# pi-crust.net
KiCad netlist of a schematic drawn in EAGLE
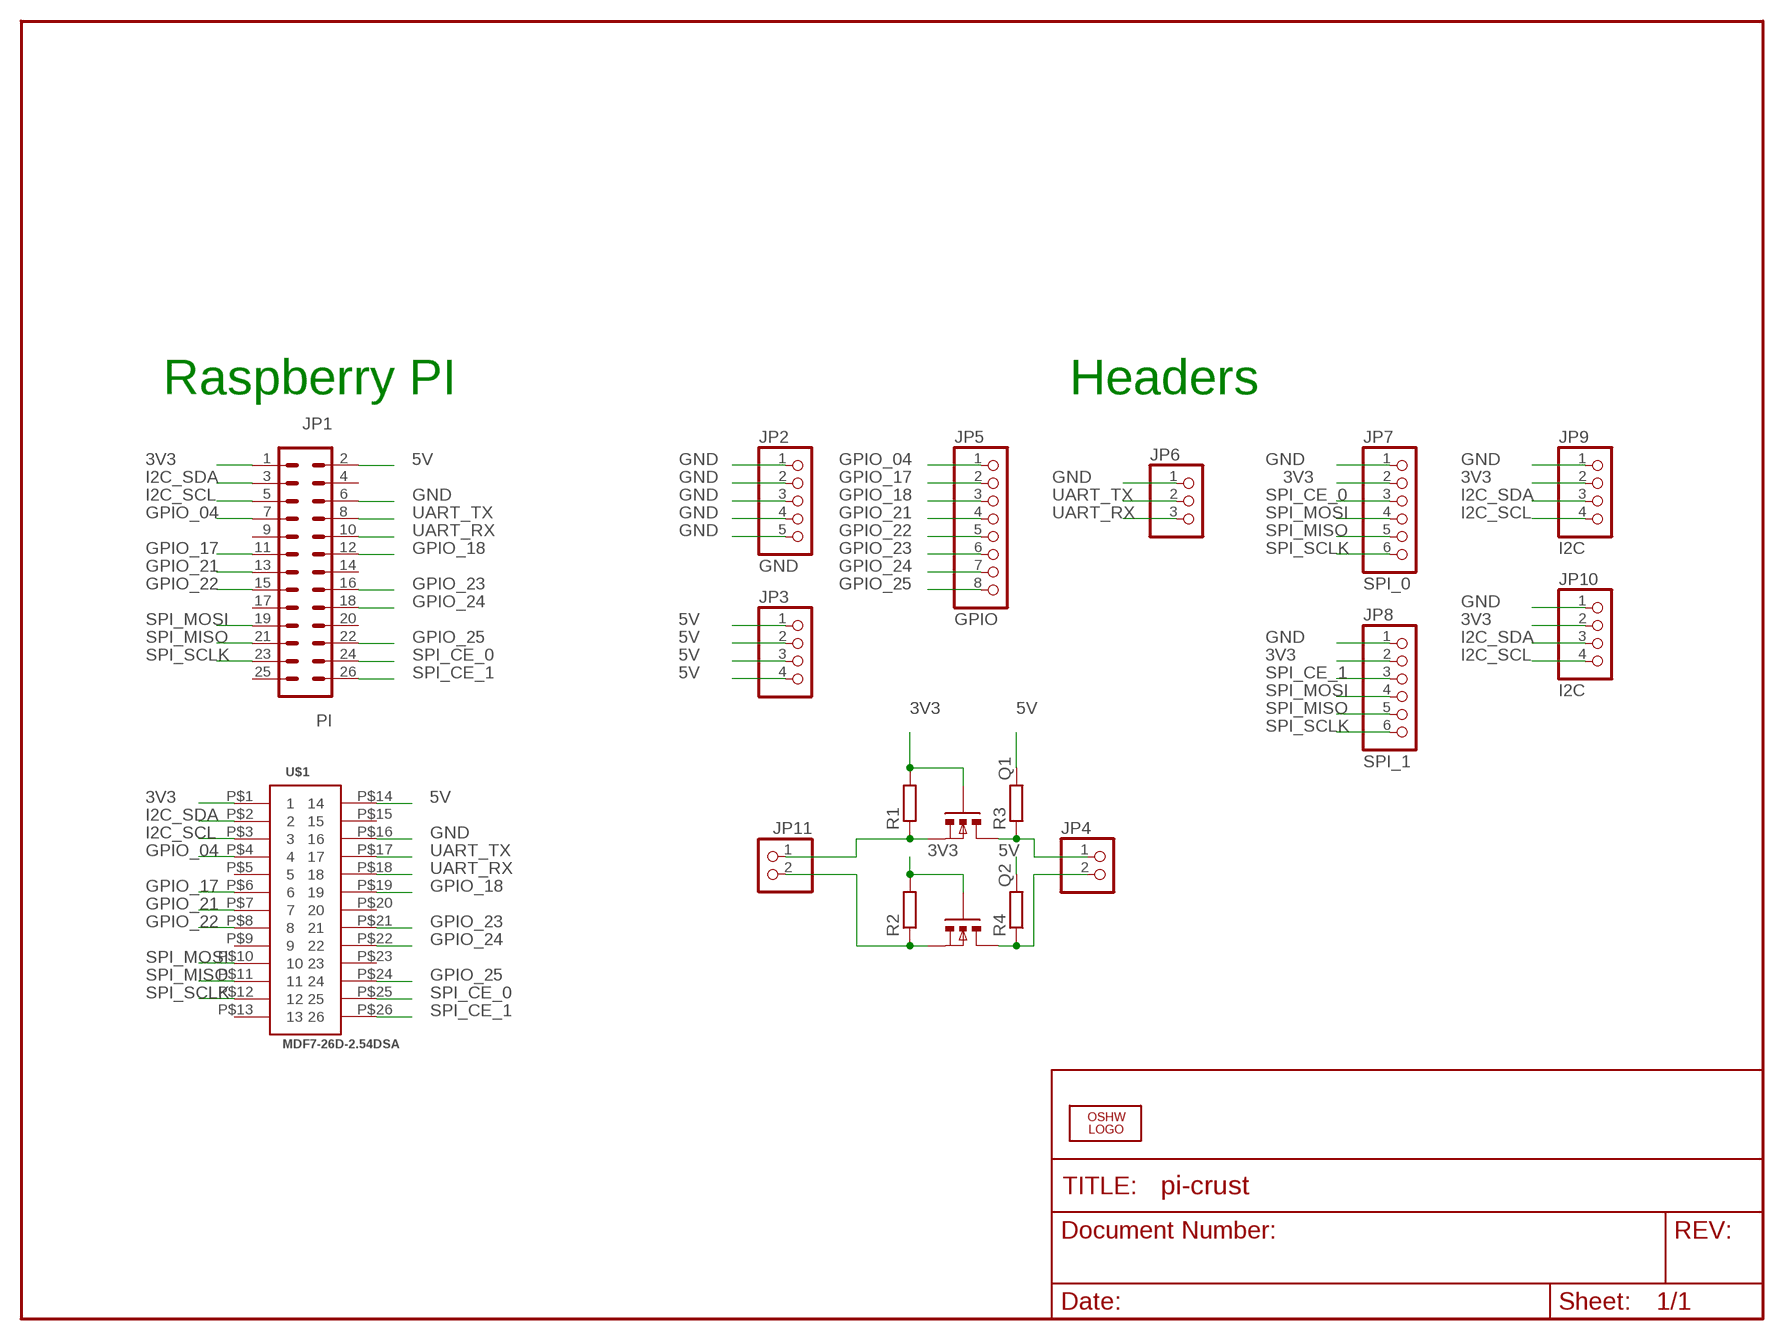
[diagram p0: schematic, sheet 1]

(export (version "E")
  (design (tool "Eeschema 10.0.6"))
  (components
    (comp (ref "JP1")
      (value "PI")
      (footprint "eagle-import:MA13-2")
      (libsource (lib "eagle-import") (part "MA13-2"))
    )
    (comp (ref "JP2")
      (value "GND")
      (footprint "eagle-import:1X05")
      (libsource (lib "eagle-import") (part "PINHD-1X5"))
    )
    (comp (ref "JP3")
      (value "PINHD-1X4")
      (footprint "eagle-import:1X04")
      (libsource (lib "eagle-import") (part "PINHD-1X4"))
    )
    (comp (ref "JP4")
      (value "PINHD-1X2")
      (footprint "eagle-import:1X02")
      (libsource (lib "eagle-import") (part "PINHD-1X2"))
    )
    (comp (ref "JP5")
      (value "GPIO")
      (footprint "eagle-import:1X08")
      (libsource (lib "eagle-import") (part "PINHD-1X8"))
    )
    (comp (ref "JP6")
      (value "PINHD-1X3")
      (footprint "eagle-import:1X03")
      (libsource (lib "eagle-import") (part "PINHD-1X3"))
    )
    (comp (ref "JP7")
      (value "SPI_0")
      (footprint "eagle-import:1X06")
      (libsource (lib "eagle-import") (part "PINHD-1X6"))
    )
    (comp (ref "JP8")
      (value "SPI_1")
      (footprint "eagle-import:1X06")
      (libsource (lib "eagle-import") (part "PINHD-1X6"))
    )
    (comp (ref "JP9")
      (value "I2C")
      (footprint "eagle-import:1X04")
      (libsource (lib "eagle-import") (part "PINHD-1X4"))
    )
    (comp (ref "JP10")
      (value "I2C")
      (footprint "eagle-import:1X04")
      (libsource (lib "eagle-import") (part "PINHD-1X4"))
    )
    (comp (ref "JP11")
      (value "PINHD-1X2")
      (footprint "eagle-import:1X02")
      (libsource (lib "eagle-import") (part "PINHD-1X2"))
    )
    (comp (ref "LOGO1")
      (value "OSHW_LOGO_8MILX0100-NT")
      (footprint "eagle-import:OSHW_8X100_NOTEXT")
      (libsource (lib "eagle-import") (part "OSHW_LOGO_8MILX0100-NT"))
    )
    (comp (ref "Q1")
      (value "BSS138SMD")
      (footprint "eagle-import:SOT23")
      (libsource (lib "eagle-import") (part "BSS138SMD"))
    )
    (comp (ref "Q2")
      (value "BSS138SMD")
      (footprint "eagle-import:SOT23")
      (libsource (lib "eagle-import") (part "BSS138SMD"))
    )
    (comp (ref "R1")
      (value "R-EU_R0603")
      (footprint "eagle-import:R0603")
      (libsource (lib "eagle-import") (part "R-EU_R0603"))
    )
    (comp (ref "R2")
      (value "R-EU_R0603")
      (footprint "eagle-import:R0603")
      (libsource (lib "eagle-import") (part "R-EU_R0603"))
    )
    (comp (ref "R3")
      (value "R-EU_R0603")
      (footprint "eagle-import:R0603")
      (libsource (lib "eagle-import") (part "R-EU_R0603"))
    )
    (comp (ref "R4")
      (value "R-EU_R0603")
      (footprint "eagle-import:R0603")
      (libsource (lib "eagle-import") (part "R-EU_R0603"))
    )
    (comp (ref "U$1")
      (value "MDF7-26D-2.54DSA")
      (footprint "eagle-import:MDF7-26D-2.54DSA")
      (libsource (lib "eagle-import") (part "MDF7-26D-2.54DSA"))
    )
  )
  (nets
    (net (code "1") (name "/3V3") (class "Default")
      (node (ref "JP1") (pin "1") (pinfunction "1_1") (pintype "passive"))
      (node (ref "JP10") (pin "2") (pinfunction "2_2") (pintype "passive"))
      (node (ref "JP7") (pin "2") (pinfunction "2_2") (pintype "passive"))
      (node (ref "JP8") (pin "2") (pinfunction "2_2") (pintype "passive"))
      (node (ref "JP9") (pin "2") (pinfunction "2_2") (pintype "passive"))
      (node (ref "Q1") (pin "2") (pinfunction "G_2") (pintype "passive"))
      (node (ref "Q2") (pin "2") (pinfunction "G_2") (pintype "passive"))
      (node (ref "R1") (pin "2") (pinfunction "2_2") (pintype "passive"))
      (node (ref "R2") (pin "2") (pinfunction "2_2") (pintype "passive"))
      (node (ref "U$1") (pin "P$1") (pinfunction "1_P$1") (pintype "bidirectional"))
    )
    (net (code "2") (name "/5V") (class "Default")
      (node (ref "JP1") (pin "2") (pinfunction "2_2") (pintype "passive"))
      (node (ref "JP3") (pin "1") (pinfunction "1_1") (pintype "passive"))
      (node (ref "JP3") (pin "2") (pinfunction "2_2") (pintype "passive"))
      (node (ref "JP3") (pin "3") (pinfunction "3_3") (pintype "passive"))
      (node (ref "JP3") (pin "4") (pinfunction "4_4") (pintype "passive"))
      (node (ref "R3") (pin "2") (pinfunction "2_2") (pintype "passive"))
      (node (ref "R4") (pin "2") (pinfunction "2_2") (pintype "passive"))
      (node (ref "U$1") (pin "P$14") (pinfunction "14_P$14") (pintype "bidirectional"))
    )
    (net (code "3") (name "/GND") (class "Default")
      (node (ref "JP1") (pin "6") (pinfunction "6_6") (pintype "passive"))
      (node (ref "JP10") (pin "1") (pinfunction "1_1") (pintype "passive"))
      (node (ref "JP2") (pin "1") (pinfunction "1_1") (pintype "passive"))
      (node (ref "JP2") (pin "2") (pinfunction "2_2") (pintype "passive"))
      (node (ref "JP2") (pin "3") (pinfunction "3_3") (pintype "passive"))
      (node (ref "JP2") (pin "4") (pinfunction "4_4") (pintype "passive"))
      (node (ref "JP2") (pin "5") (pinfunction "5_5") (pintype "passive"))
      (node (ref "JP6") (pin "1") (pinfunction "1_1") (pintype "passive"))
      (node (ref "JP7") (pin "1") (pinfunction "1_1") (pintype "passive"))
      (node (ref "JP8") (pin "1") (pinfunction "1_1") (pintype "passive"))
      (node (ref "JP9") (pin "1") (pinfunction "1_1") (pintype "passive"))
      (node (ref "U$1") (pin "P$16") (pinfunction "16_P$16") (pintype "bidirectional"))
    )
    (net (code "4") (name "/GPIO_04") (class "Default")
      (node (ref "JP1") (pin "7") (pinfunction "7_7") (pintype "passive"))
      (node (ref "JP5") (pin "1") (pinfunction "1_1") (pintype "passive"))
      (node (ref "U$1") (pin "P$4") (pinfunction "4_P$4") (pintype "bidirectional"))
    )
    (net (code "5") (name "/GPIO_17") (class "Default")
      (node (ref "JP1") (pin "11") (pinfunction "11_11") (pintype "passive"))
      (node (ref "JP5") (pin "2") (pinfunction "2_2") (pintype "passive"))
      (node (ref "U$1") (pin "P$6") (pinfunction "6_P$6") (pintype "bidirectional"))
    )
    (net (code "6") (name "/GPIO_18") (class "Default")
      (node (ref "JP1") (pin "12") (pinfunction "12_12") (pintype "passive"))
      (node (ref "JP5") (pin "3") (pinfunction "3_3") (pintype "passive"))
      (node (ref "U$1") (pin "P$19") (pinfunction "19_P$19") (pintype "bidirectional"))
    )
    (net (code "7") (name "/GPIO_21") (class "Default")
      (node (ref "JP1") (pin "13") (pinfunction "13_13") (pintype "passive"))
      (node (ref "JP5") (pin "4") (pinfunction "4_4") (pintype "passive"))
      (node (ref "U$1") (pin "P$7") (pinfunction "7_P$7") (pintype "bidirectional"))
    )
    (net (code "8") (name "/GPIO_22") (class "Default")
      (node (ref "JP1") (pin "15") (pinfunction "15_15") (pintype "passive"))
      (node (ref "JP5") (pin "5") (pinfunction "5_5") (pintype "passive"))
      (node (ref "U$1") (pin "P$8") (pinfunction "8_P$8") (pintype "bidirectional"))
    )
    (net (code "9") (name "/GPIO_23") (class "Default")
      (node (ref "JP1") (pin "16") (pinfunction "16_16") (pintype "passive"))
      (node (ref "JP5") (pin "6") (pinfunction "6_6") (pintype "passive"))
      (node (ref "U$1") (pin "P$21") (pinfunction "21_P$21") (pintype "bidirectional"))
    )
    (net (code "10") (name "/GPIO_24") (class "Default")
      (node (ref "JP1") (pin "18") (pinfunction "18_18") (pintype "passive"))
      (node (ref "JP5") (pin "7") (pinfunction "7_7") (pintype "passive"))
      (node (ref "U$1") (pin "P$22") (pinfunction "22_P$22") (pintype "bidirectional"))
    )
    (net (code "11") (name "/GPIO_25") (class "Default")
      (node (ref "JP1") (pin "22") (pinfunction "22_22") (pintype "passive"))
      (node (ref "JP5") (pin "8") (pinfunction "8_8") (pintype "passive"))
      (node (ref "U$1") (pin "P$24") (pinfunction "24_P$24") (pintype "bidirectional"))
    )
    (net (code "12") (name "/I2C_SCL") (class "Default")
      (node (ref "JP1") (pin "5") (pinfunction "5_5") (pintype "passive"))
      (node (ref "JP10") (pin "4") (pinfunction "4_4") (pintype "passive"))
      (node (ref "JP9") (pin "4") (pinfunction "4_4") (pintype "passive"))
      (node (ref "U$1") (pin "P$3") (pinfunction "3_P$3") (pintype "bidirectional"))
    )
    (net (code "13") (name "/I2C_SDA") (class "Default")
      (node (ref "JP1") (pin "3") (pinfunction "3_3") (pintype "passive"))
      (node (ref "JP10") (pin "3") (pinfunction "3_3") (pintype "passive"))
      (node (ref "JP9") (pin "3") (pinfunction "3_3") (pintype "passive"))
      (node (ref "U$1") (pin "P$2") (pinfunction "2_P$2") (pintype "bidirectional"))
    )
    (net (code "14") (name "/SPI_CE_0") (class "Default")
      (node (ref "JP1") (pin "24") (pinfunction "24_24") (pintype "passive"))
      (node (ref "JP7") (pin "3") (pinfunction "3_3") (pintype "passive"))
      (node (ref "U$1") (pin "P$25") (pinfunction "25_P$25") (pintype "bidirectional"))
    )
    (net (code "15") (name "/SPI_CE_1") (class "Default")
      (node (ref "JP1") (pin "26") (pinfunction "26_26") (pintype "passive"))
      (node (ref "JP8") (pin "3") (pinfunction "3_3") (pintype "passive"))
      (node (ref "U$1") (pin "P$26") (pinfunction "26_P$26") (pintype "bidirectional"))
    )
    (net (code "16") (name "/SPI_MISO") (class "Default")
      (node (ref "JP1") (pin "21") (pinfunction "21_21") (pintype "passive"))
      (node (ref "JP7") (pin "5") (pinfunction "5_5") (pintype "passive"))
      (node (ref "JP8") (pin "5") (pinfunction "5_5") (pintype "passive"))
      (node (ref "U$1") (pin "P$11") (pinfunction "11_P$11") (pintype "bidirectional"))
    )
    (net (code "17") (name "/SPI_MOSI") (class "Default")
      (node (ref "JP1") (pin "19") (pinfunction "19_19") (pintype "passive"))
      (node (ref "JP7") (pin "4") (pinfunction "4_4") (pintype "passive"))
      (node (ref "JP8") (pin "4") (pinfunction "4_4") (pintype "passive"))
      (node (ref "U$1") (pin "P$10") (pinfunction "10_P$10") (pintype "bidirectional"))
    )
    (net (code "18") (name "/SPI_SCLK") (class "Default")
      (node (ref "JP1") (pin "23") (pinfunction "23_23") (pintype "passive"))
      (node (ref "JP7") (pin "6") (pinfunction "6_6") (pintype "passive"))
      (node (ref "JP8") (pin "6") (pinfunction "6_6") (pintype "passive"))
      (node (ref "U$1") (pin "P$12") (pinfunction "12_P$12") (pintype "bidirectional"))
    )
    (net (code "19") (name "/UART_RX") (class "Default")
      (node (ref "JP1") (pin "10") (pinfunction "10_10") (pintype "passive"))
      (node (ref "JP6") (pin "3") (pinfunction "3_3") (pintype "passive"))
      (node (ref "U$1") (pin "P$18") (pinfunction "18_P$18") (pintype "bidirectional"))
    )
    (net (code "20") (name "/UART_TX") (class "Default")
      (node (ref "JP1") (pin "8") (pinfunction "8_8") (pintype "passive"))
      (node (ref "JP6") (pin "2") (pinfunction "2_2") (pintype "passive"))
      (node (ref "U$1") (pin "P$17") (pinfunction "17_P$17") (pintype "bidirectional"))
    )
    (net (code "21") (name "Net-(Q1-D)") (class "Default")
      (node (ref "JP4") (pin "1") (pinfunction "1_1") (pintype "passive"))
      (node (ref "Q1") (pin "3") (pinfunction "D_3") (pintype "passive"))
      (node (ref "R3") (pin "1") (pinfunction "1_1") (pintype "passive"))
    )
    (net (code "22") (name "Net-(Q1-S)") (class "Default")
      (node (ref "JP11") (pin "1") (pinfunction "1_1") (pintype "passive"))
      (node (ref "Q1") (pin "1") (pinfunction "S_1") (pintype "passive"))
      (node (ref "R1") (pin "1") (pinfunction "1_1") (pintype "passive"))
    )
    (net (code "23") (name "Net-(Q2-D)") (class "Default")
      (node (ref "JP4") (pin "2") (pinfunction "2_2") (pintype "passive"))
      (node (ref "Q2") (pin "3") (pinfunction "D_3") (pintype "passive"))
      (node (ref "R4") (pin "1") (pinfunction "1_1") (pintype "passive"))
    )
    (net (code "24") (name "Net-(Q2-S)") (class "Default")
      (node (ref "JP11") (pin "2") (pinfunction "2_2") (pintype "passive"))
      (node (ref "Q2") (pin "1") (pinfunction "S_1") (pintype "passive"))
      (node (ref "R2") (pin "1") (pinfunction "1_1") (pintype "passive"))
    )
    (net (code "25") (name "unconnected-(JP1-Pad4)") (class "Default")
      (node (ref "JP1") (pin "4") (pinfunction "4_4") (pintype "passive"))
    )
    (net (code "26") (name "unconnected-(JP1-Pad9)") (class "Default")
      (node (ref "JP1") (pin "9") (pinfunction "9_9") (pintype "passive"))
    )
    (net (code "27") (name "unconnected-(JP1-Pad14)") (class "Default")
      (node (ref "JP1") (pin "14") (pinfunction "14_14") (pintype "passive"))
    )
    (net (code "28") (name "unconnected-(JP1-Pad17)") (class "Default")
      (node (ref "JP1") (pin "17") (pinfunction "17_17") (pintype "passive"))
    )
    (net (code "29") (name "unconnected-(JP1-Pad20)") (class "Default")
      (node (ref "JP1") (pin "20") (pinfunction "20_20") (pintype "passive"))
    )
    (net (code "30") (name "unconnected-(JP1-Pad25)") (class "Default")
      (node (ref "JP1") (pin "25") (pinfunction "25_25") (pintype "passive"))
    )
    (net (code "31") (name "unconnected-(U$1-5-PadP$5)") (class "Default")
      (node (ref "U$1") (pin "P$5") (pinfunction "5_P$5") (pintype "bidirectional"))
    )
    (net (code "32") (name "unconnected-(U$1-9-PadP$9)") (class "Default")
      (node (ref "U$1") (pin "P$9") (pinfunction "9_P$9") (pintype "bidirectional"))
    )
    (net (code "33") (name "unconnected-(U$1-13-PadP$13)") (class "Default")
      (node (ref "U$1") (pin "P$13") (pinfunction "13_P$13") (pintype "bidirectional"))
    )
    (net (code "34") (name "unconnected-(U$1-15-PadP$15)") (class "Default")
      (node (ref "U$1") (pin "P$15") (pinfunction "15_P$15") (pintype "bidirectional"))
    )
    (net (code "35") (name "unconnected-(U$1-20-PadP$20)") (class "Default")
      (node (ref "U$1") (pin "P$20") (pinfunction "20_P$20") (pintype "bidirectional"))
    )
    (net (code "36") (name "unconnected-(U$1-23-PadP$23)") (class "Default")
      (node (ref "U$1") (pin "P$23") (pinfunction "23_P$23") (pintype "bidirectional"))
    )
  )
)
